# SWD-ud-a-01.net
KiCad netlist of a schematic drawn in EAGLE
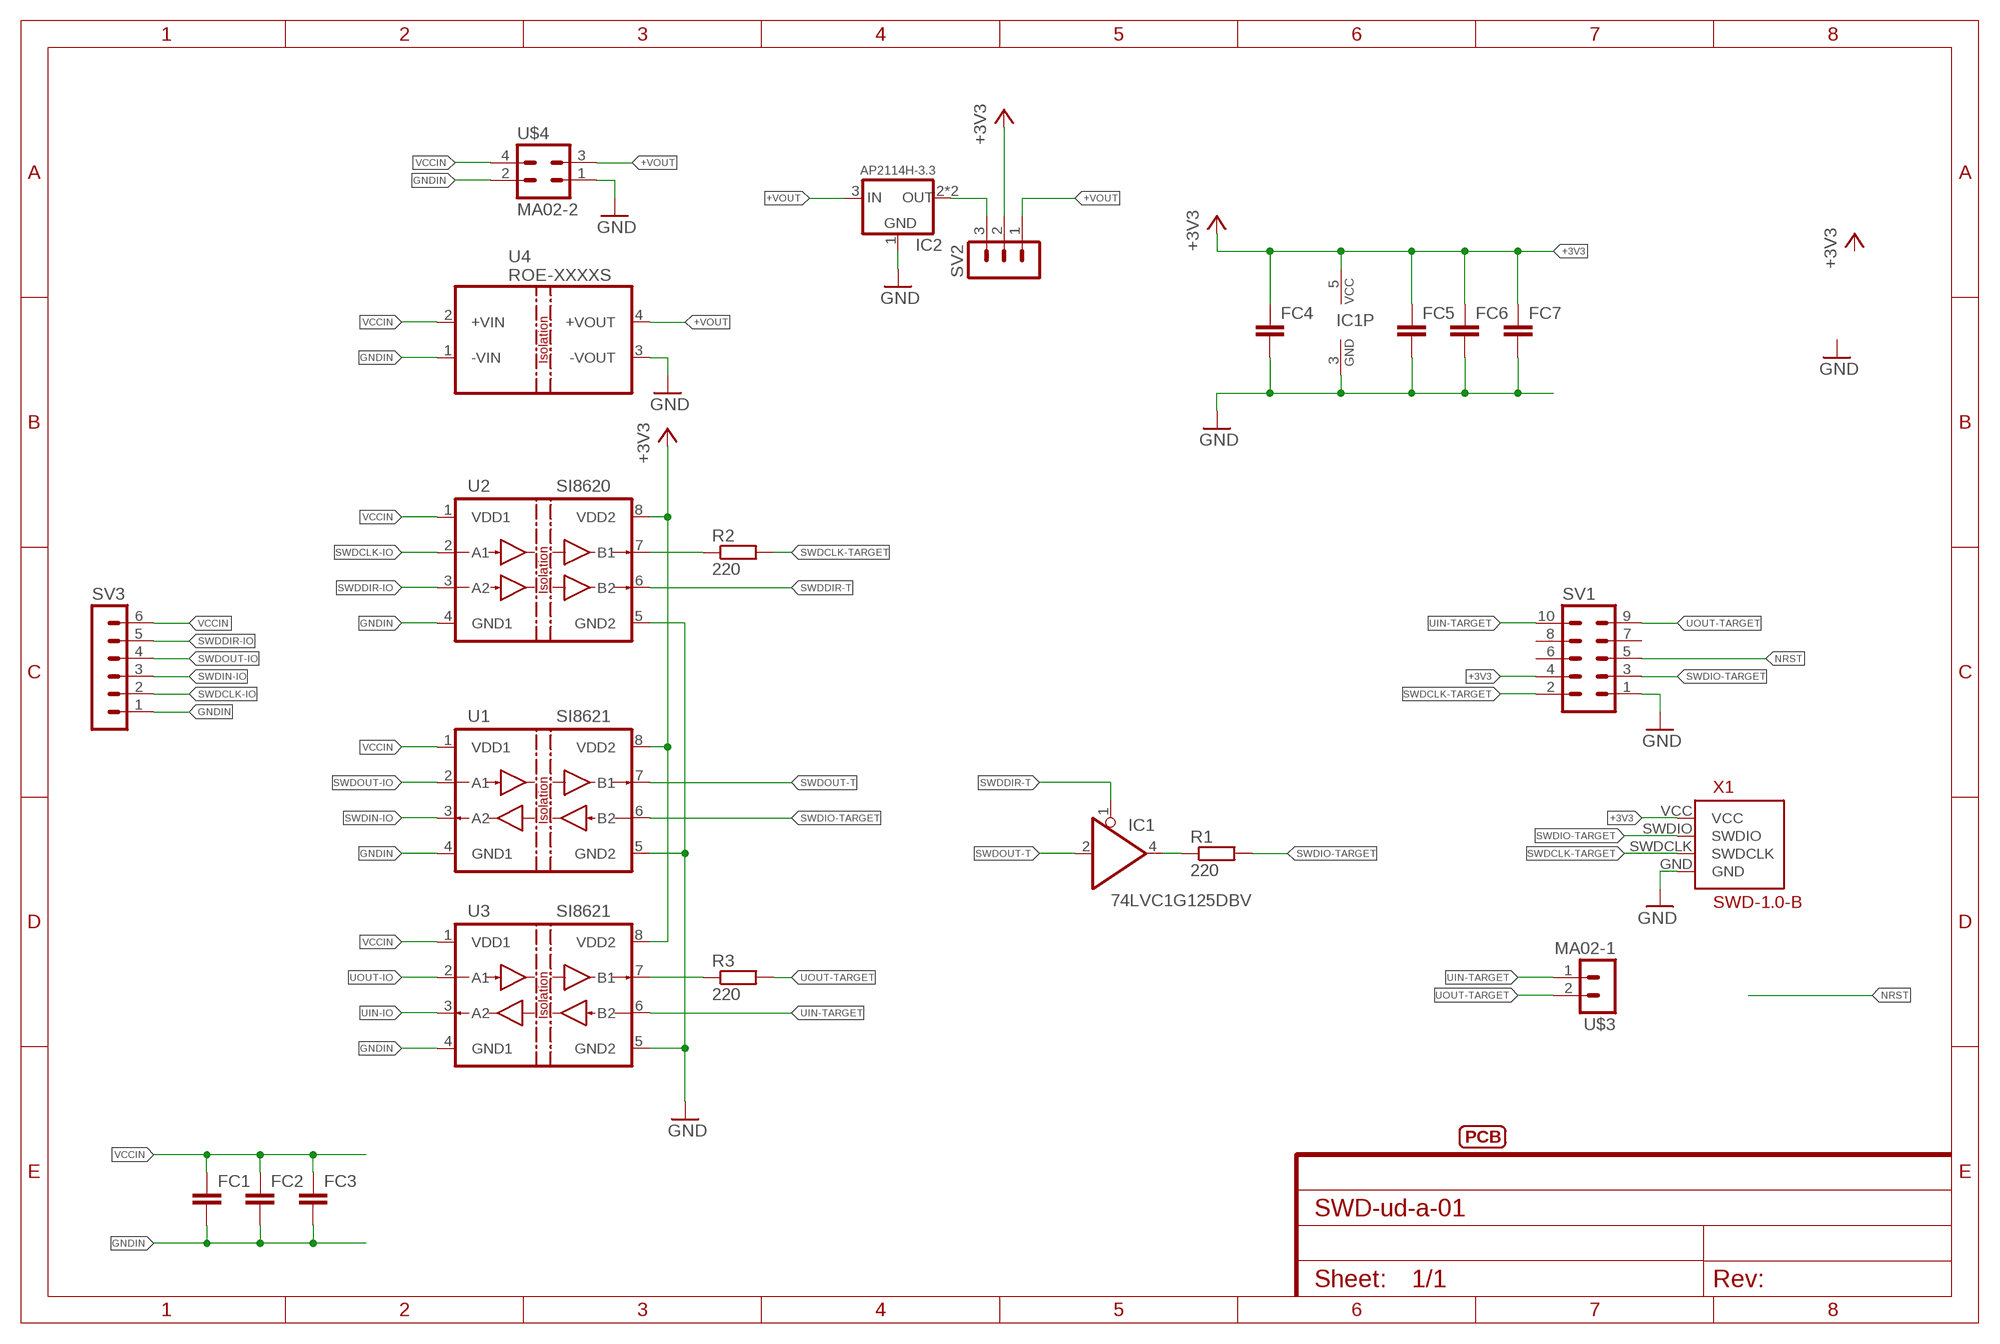
[diagram p0: schematic, sheet 1]

(export (version "E")
  (design (tool "Eeschema 10.0.6"))
  (components
    (comp (ref "FC1")
      (value "C-EUC0805")
      (footprint "eagle-import:C0805")
      (libsource (lib "eagle-import") (part "C-EUC0805"))
    )
    (comp (ref "FC2")
      (value "C-EUC0805")
      (footprint "eagle-import:C0805")
      (libsource (lib "eagle-import") (part "C-EUC0805"))
    )
    (comp (ref "FC3")
      (value "C-EUC0805")
      (footprint "eagle-import:C0805")
      (libsource (lib "eagle-import") (part "C-EUC0805"))
    )
    (comp (ref "FC4")
      (value "C-EUC0805")
      (footprint "eagle-import:C0805")
      (libsource (lib "eagle-import") (part "C-EUC0805"))
    )
    (comp (ref "FC5")
      (value "C-EUC0805")
      (footprint "eagle-import:C0805")
      (libsource (lib "eagle-import") (part "C-EUC0805"))
    )
    (comp (ref "FC6")
      (value "C-EUC0805")
      (footprint "eagle-import:C0805")
      (libsource (lib "eagle-import") (part "C-EUC0805"))
    )
    (comp (ref "FC7")
      (value "C-EUC0805")
      (footprint "eagle-import:C0805")
      (libsource (lib "eagle-import") (part "C-EUC0805"))
    )
    (comp (ref "IC1")
      (value "74LVC1G125DBV")
      (footprint "eagle-import:SOT23-5")
      (libsource (lib "eagle-import") (part "741G125DBVLVC"))
    )
    (comp (ref "IC2")
      (value "AP2114H-3.3")
      (footprint "eagle-import:SOT223")
      (fields (field (name "PARTNO") "AP2114H-3.3TRG1DICT-ND"))
      (libsource (lib "eagle-import") (part "AP2114H"))
    )
    (comp (ref "R1")
      (value "220")
      (footprint "eagle-import:R0603")
      (libsource (lib "eagle-import") (part "R-EU_R0603"))
    )
    (comp (ref "R2")
      (value "220")
      (footprint "eagle-import:R0603")
      (libsource (lib "eagle-import") (part "R-EU_R0603"))
    )
    (comp (ref "R3")
      (value "220")
      (footprint "eagle-import:R0603")
      (libsource (lib "eagle-import") (part "R-EU_R0603"))
    )
    (comp (ref "SV1")
      (value "MA05-2")
      (footprint "eagle-import:MA05-2")
      (libsource (lib "eagle-import") (part "MA05-2"))
    )
    (comp (ref "SV2")
      (value "MA03-1")
      (footprint "eagle-import:MA03-1")
      (libsource (lib "eagle-import") (part "MA03-1"))
    )
    (comp (ref "SV3")
      (value "MA06-1")
      (footprint "eagle-import:MA06-1")
      (libsource (lib "eagle-import") (part "MA06-1"))
    )
    (comp (ref "U$2")
      (value "ENCLOSURE-CN-60X54")
      (footprint "eagle-import:ENCLOSURE-CN-60X54")
      (libsource (lib "eagle-import") (part "ENCLOSURE-CN-60X54"))
    )
    (comp (ref "U$3")
      (value "MA02-1")
      (footprint "eagle-import:MA02-1")
      (libsource (lib "eagle-import") (part "MA02-1"))
    )
    (comp (ref "U$4")
      (value "MA02-2")
      (footprint "eagle-import:MA02-2")
      (libsource (lib "eagle-import") (part "MA02-2"))
    )
    (comp (ref "U1")
      (value "SI8621")
      (footprint "eagle-import:SOIC-8")
      (libsource (lib "eagle-import") (part "SI8421"))
    )
    (comp (ref "U2")
      (value "SI8620")
      (footprint "eagle-import:SOIC-8")
      (libsource (lib "eagle-import") (part "SI8620"))
    )
    (comp (ref "U3")
      (value "SI8621")
      (footprint "eagle-import:SOIC-8")
      (libsource (lib "eagle-import") (part "SI8421"))
    )
    (comp (ref "U4")
      (value "ROE-XXXXS")
      (footprint "eagle-import:ROE-SIP-4")
      (libsource (lib "eagle-import") (part "ROE-XXXXS"))
    )
    (comp (ref "X1")
      (value "SWD-1.0-B")
      (footprint "eagle-import:SWD-1.0-B")
      (libsource (lib "eagle-import") (part "SWD-1.0-B"))
    )
  )
  (nets
    (net (code "1") (name "+3V3") (class "Default")
      (node (ref "FC4") (pin "1") (pinfunction "1_1") (pintype "passive"))
      (node (ref "FC5") (pin "1") (pinfunction "1_1") (pintype "passive"))
      (node (ref "FC6") (pin "1") (pinfunction "1_1") (pintype "passive"))
      (node (ref "FC7") (pin "1") (pinfunction "1_1") (pintype "passive"))
      (node (ref "IC1") (pin "5") (pinfunction "VCC_5") (pintype "power_in"))
      (node (ref "SV1") (pin "4") (pinfunction "4_4") (pintype "passive"))
      (node (ref "SV2") (pin "2") (pinfunction "2_2") (pintype "passive"))
      (node (ref "U1") (pin "8") (pinfunction "VDD2_8") (pintype "power_in"))
      (node (ref "U2") (pin "8") (pinfunction "VDD2_8") (pintype "power_in"))
      (node (ref "U3") (pin "8") (pinfunction "VDD2_8") (pintype "power_in"))
      (node (ref "X1") (pin "VCC") (pinfunction "VCC_VCC") (pintype "bidirectional"))
    )
    (net (code "2") (name "+VOUT") (class "Default")
      (node (ref "IC2") (pin "3") (pinfunction "IN_3") (pintype "input"))
      (node (ref "SV2") (pin "1") (pinfunction "1_1") (pintype "passive"))
      (node (ref "U$4") (pin "3") (pinfunction "3_3") (pintype "passive"))
      (node (ref "U4") (pin "4") (pinfunction "+VOUT_4") (pintype "passive"))
    )
    (net (code "3") (name "GND") (class "Default")
      (node (ref "FC4") (pin "2") (pinfunction "2_2") (pintype "passive"))
      (node (ref "FC5") (pin "2") (pinfunction "2_2") (pintype "passive"))
      (node (ref "FC6") (pin "2") (pinfunction "2_2") (pintype "passive"))
      (node (ref "FC7") (pin "2") (pinfunction "2_2") (pintype "passive"))
      (node (ref "IC1") (pin "3") (pinfunction "GND_3") (pintype "power_in"))
      (node (ref "IC2") (pin "1") (pinfunction "GND_1") (pintype "input"))
      (node (ref "SV1") (pin "1") (pinfunction "1_1") (pintype "passive"))
      (node (ref "U$4") (pin "1") (pinfunction "1_1") (pintype "passive"))
      (node (ref "U1") (pin "5") (pinfunction "GND2_5") (pintype "power_in"))
      (node (ref "U2") (pin "5") (pinfunction "GND2_5") (pintype "power_in"))
      (node (ref "U3") (pin "5") (pinfunction "GND2_5") (pintype "power_in"))
      (node (ref "U4") (pin "3") (pinfunction "-VOUT_3") (pintype "passive"))
      (node (ref "X1") (pin "GND") (pinfunction "GND_GND") (pintype "bidirectional"))
    )
    (net (code "4") (name "GNDIN") (class "Default")
      (node (ref "FC1") (pin "2") (pinfunction "2_2") (pintype "passive"))
      (node (ref "FC2") (pin "2") (pinfunction "2_2") (pintype "passive"))
      (node (ref "FC3") (pin "2") (pinfunction "2_2") (pintype "passive"))
      (node (ref "SV3") (pin "1") (pinfunction "1_1") (pintype "passive"))
      (node (ref "U$4") (pin "2") (pinfunction "2_2") (pintype "passive"))
      (node (ref "U1") (pin "4") (pinfunction "GND1_4") (pintype "power_in"))
      (node (ref "U2") (pin "4") (pinfunction "GND1_4") (pintype "power_in"))
      (node (ref "U3") (pin "4") (pinfunction "GND1_4") (pintype "power_in"))
      (node (ref "U4") (pin "1") (pinfunction "-VIN_1") (pintype "passive"))
    )
    (net (code "5") (name "NRST") (class "Default")
      (node (ref "SV1") (pin "5") (pinfunction "5_5") (pintype "passive"))
    )
    (net (code "6") (name "Net-(IC1A-O)") (class "Default")
      (node (ref "IC1") (pin "4") (pinfunction "O_4") (pintype "tri_state"))
      (node (ref "R1") (pin "1") (pinfunction "1_1") (pintype "passive"))
    )
    (net (code "7") (name "Net-(IC2-OUT-Pad2)") (class "Default")
      (node (ref "IC2") (pin "2") (pinfunction "OUT_2") (pintype "passive"))
      (node (ref "IC2") (pin "TAB") (pinfunction "OUT_TAB") (pintype "passive"))
      (node (ref "SV2") (pin "3") (pinfunction "3_3") (pintype "passive"))
    )
    (net (code "8") (name "Net-(U2-B1)") (class "Default")
      (node (ref "R2") (pin "1") (pinfunction "1_1") (pintype "passive"))
      (node (ref "U2") (pin "7") (pinfunction "B1_7") (pintype "output"))
    )
    (net (code "9") (name "Net-(U3-B1)") (class "Default")
      (node (ref "R3") (pin "1") (pinfunction "1_1") (pintype "passive"))
      (node (ref "U3") (pin "7") (pinfunction "B1_7") (pintype "output"))
    )
    (net (code "10") (name "SWDCLK-IO") (class "Default")
      (node (ref "SV3") (pin "2") (pinfunction "2_2") (pintype "passive"))
      (node (ref "U2") (pin "2") (pinfunction "A1_2") (pintype "input"))
    )
    (net (code "11") (name "SWDCLK-TARGET") (class "Default")
      (node (ref "R2") (pin "2") (pinfunction "2_2") (pintype "passive"))
      (node (ref "SV1") (pin "2") (pinfunction "2_2") (pintype "passive"))
      (node (ref "X1") (pin "SWDCLK") (pinfunction "SWDCLK_SWDCLK") (pintype "bidirectional"))
    )
    (net (code "12") (name "SWDDIR-IO") (class "Default")
      (node (ref "SV3") (pin "5") (pinfunction "5_5") (pintype "passive"))
      (node (ref "U2") (pin "3") (pinfunction "A2_3") (pintype "input"))
    )
    (net (code "13") (name "SWDDIR-T") (class "Default")
      (node (ref "IC1") (pin "1") (pinfunction "OE_1") (pintype "input"))
      (node (ref "U2") (pin "6") (pinfunction "B2_6") (pintype "output"))
    )
    (net (code "14") (name "SWDIN-IO") (class "Default")
      (node (ref "SV3") (pin "3") (pinfunction "3_3") (pintype "passive"))
      (node (ref "U1") (pin "3") (pinfunction "A2_3") (pintype "output"))
    )
    (net (code "15") (name "SWDIO-TARGET") (class "Default")
      (node (ref "R1") (pin "2") (pinfunction "2_2") (pintype "passive"))
      (node (ref "SV1") (pin "3") (pinfunction "3_3") (pintype "passive"))
      (node (ref "U1") (pin "6") (pinfunction "B2_6") (pintype "input"))
      (node (ref "X1") (pin "SWDIO") (pinfunction "SWDIO_SWDIO") (pintype "bidirectional"))
    )
    (net (code "16") (name "SWDOUT-IO") (class "Default")
      (node (ref "SV3") (pin "4") (pinfunction "4_4") (pintype "passive"))
      (node (ref "U1") (pin "2") (pinfunction "A1_2") (pintype "input"))
    )
    (net (code "17") (name "SWDOUT-T") (class "Default")
      (node (ref "IC1") (pin "2") (pinfunction "I_2") (pintype "input"))
      (node (ref "U1") (pin "7") (pinfunction "B1_7") (pintype "output"))
    )
    (net (code "18") (name "UIN-IO") (class "Default")
      (node (ref "U3") (pin "3") (pinfunction "A2_3") (pintype "output"))
    )
    (net (code "19") (name "UIN-TARGET") (class "Default")
      (node (ref "SV1") (pin "10") (pinfunction "10_10") (pintype "passive"))
      (node (ref "U$3") (pin "1") (pinfunction "1_1") (pintype "passive"))
      (node (ref "U3") (pin "6") (pinfunction "B2_6") (pintype "input"))
    )
    (net (code "20") (name "UOUT-IO") (class "Default")
      (node (ref "U3") (pin "2") (pinfunction "A1_2") (pintype "input"))
    )
    (net (code "21") (name "UOUT-TARGET") (class "Default")
      (node (ref "R3") (pin "2") (pinfunction "2_2") (pintype "passive"))
      (node (ref "SV1") (pin "9") (pinfunction "9_9") (pintype "passive"))
      (node (ref "U$3") (pin "2") (pinfunction "2_2") (pintype "passive"))
    )
    (net (code "22") (name "VCCIN") (class "Default")
      (node (ref "FC1") (pin "1") (pinfunction "1_1") (pintype "passive"))
      (node (ref "FC2") (pin "1") (pinfunction "1_1") (pintype "passive"))
      (node (ref "FC3") (pin "1") (pinfunction "1_1") (pintype "passive"))
      (node (ref "SV3") (pin "6") (pinfunction "6_6") (pintype "passive"))
      (node (ref "U$4") (pin "4") (pinfunction "4_4") (pintype "passive"))
      (node (ref "U1") (pin "1") (pinfunction "VDD1_1") (pintype "power_in"))
      (node (ref "U2") (pin "1") (pinfunction "VDD1_1") (pintype "power_in"))
      (node (ref "U3") (pin "1") (pinfunction "VDD1_1") (pintype "power_in"))
      (node (ref "U4") (pin "2") (pinfunction "+VIN_2") (pintype "passive"))
    )
    (net (code "23") (name "unconnected-(SV1-Pad6)") (class "Default")
      (node (ref "SV1") (pin "6") (pinfunction "6_6") (pintype "passive"))
    )
    (net (code "24") (name "unconnected-(SV1-Pad7)") (class "Default")
      (node (ref "SV1") (pin "7") (pinfunction "7_7") (pintype "passive"))
    )
    (net (code "25") (name "unconnected-(SV1-Pad8)") (class "Default")
      (node (ref "SV1") (pin "8") (pinfunction "8_8") (pintype "passive"))
    )
  )
)
